# Voicecard-SMR-v04.net
KiCad netlist of a schematic drawn in EAGLE
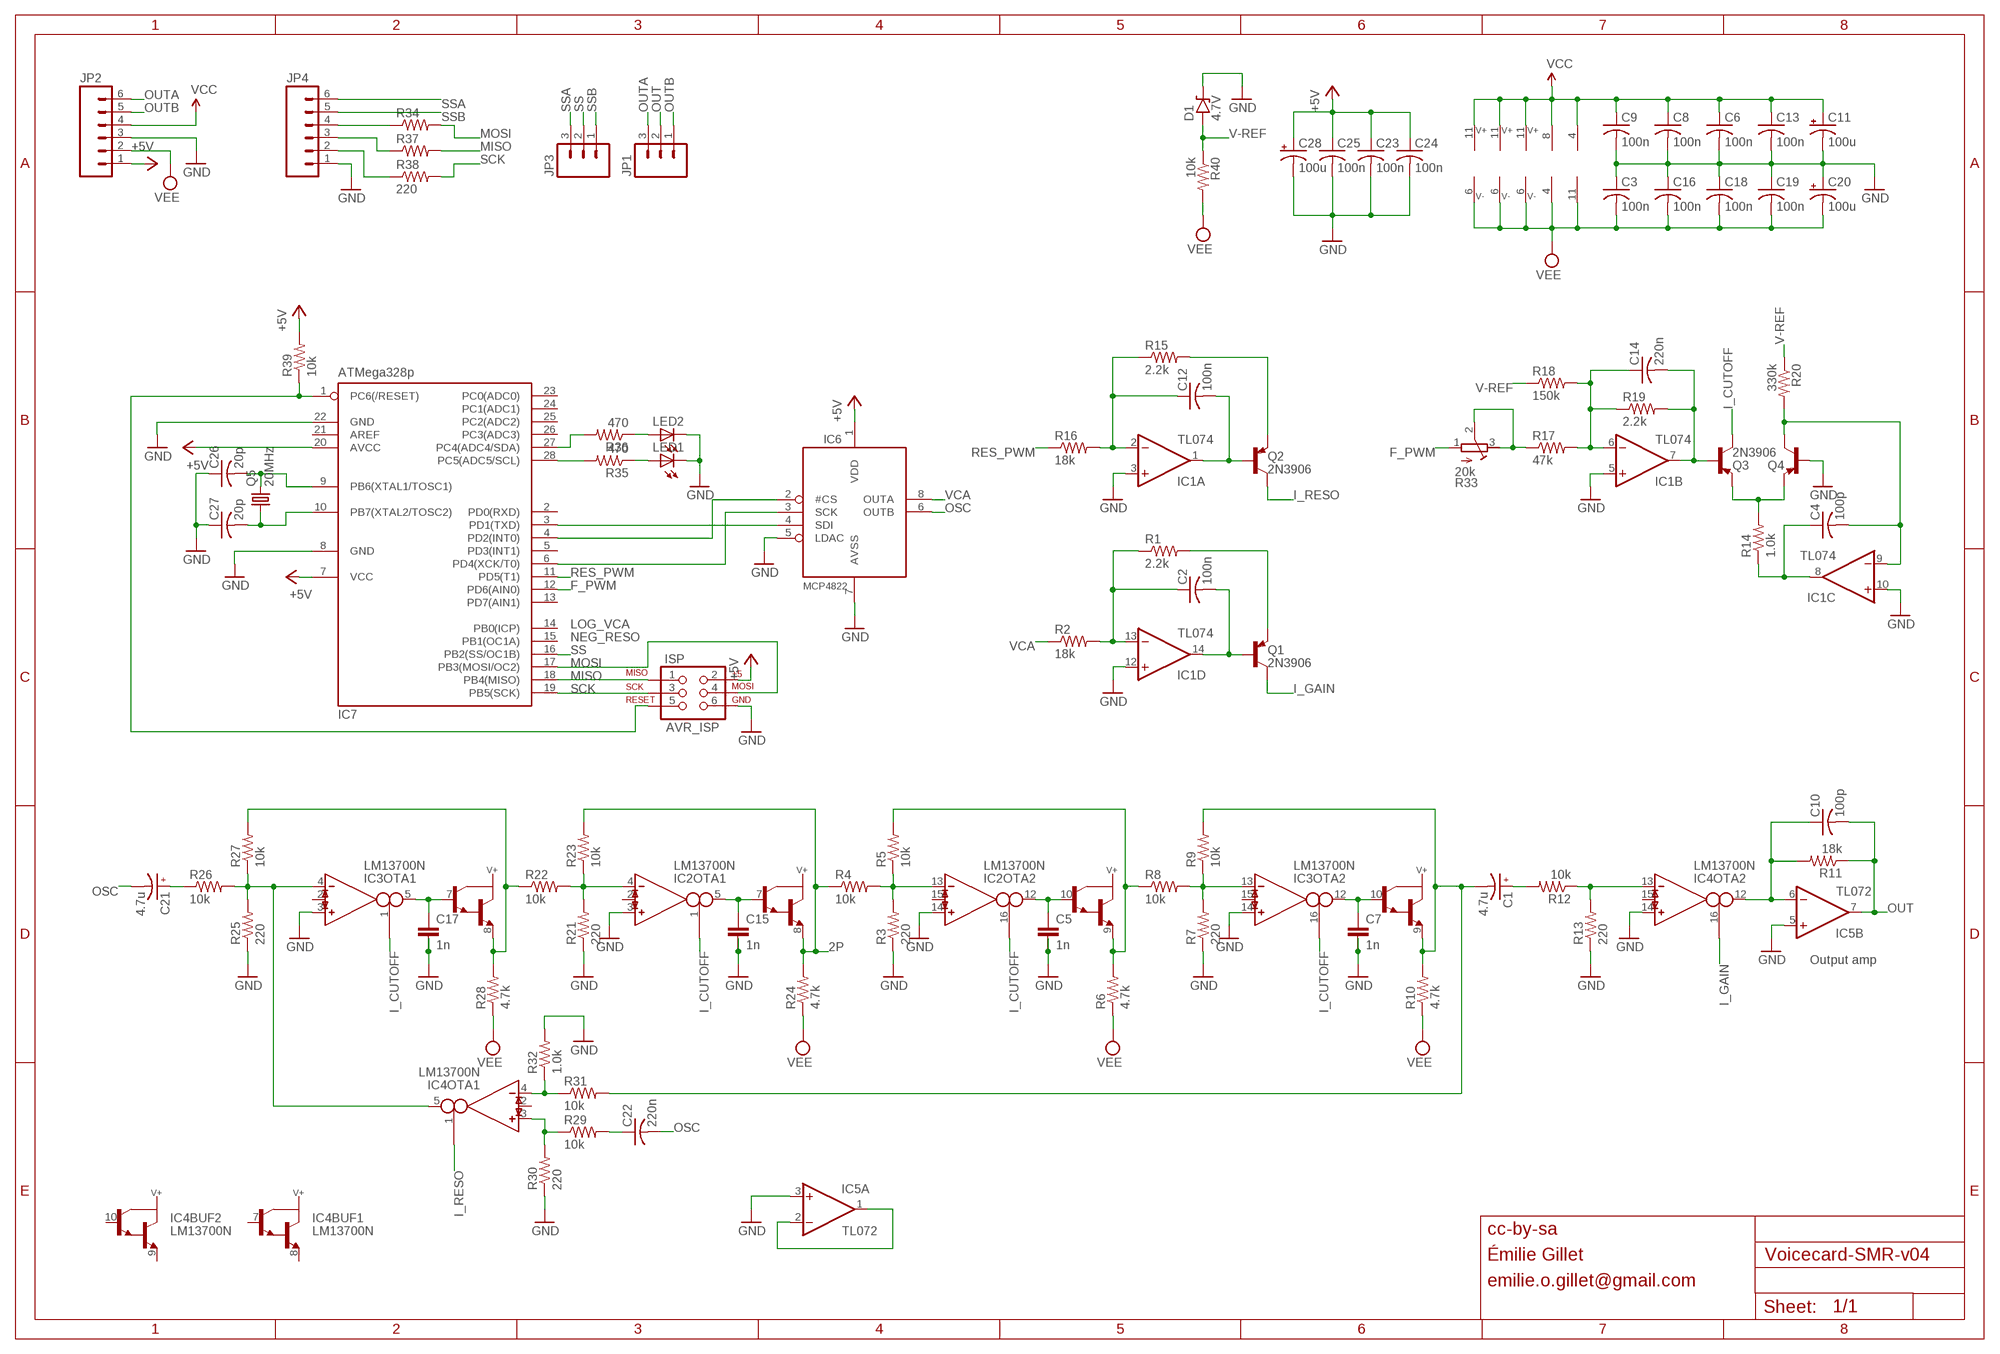
[diagram p0: schematic, sheet 1]

(export (version "E")
  (design (tool "Eeschema 10.0.6"))
  (components
    (comp (ref "C1")
      (value "4.7u")
      (footprint "eagle-import:E11-6.3")
      (libsource (lib "eagle-import") (part "CPOL-USE11-6.3"))
    )
    (comp (ref "C2")
      (value "100n")
      (footprint "eagle-import:C025-025X050")
      (libsource (lib "eagle-import") (part "C-US025-025X050"))
    )
    (comp (ref "C3")
      (value "100n")
      (footprint "eagle-import:C025-025X050")
      (libsource (lib "eagle-import") (part "C-US025-025X050"))
    )
    (comp (ref "C4")
      (value "100p")
      (footprint "eagle-import:C025-025X050")
      (libsource (lib "eagle-import") (part "C-US025-025X050"))
    )
    (comp (ref "C5")
      (value "1n")
      (footprint "eagle-import:C2.5_5-2")
      (libsource (lib "eagle-import") (part "C-2.5-5/2"))
    )
    (comp (ref "C6")
      (value "100n")
      (footprint "eagle-import:C025-025X050")
      (libsource (lib "eagle-import") (part "C-US025-025X050"))
    )
    (comp (ref "C7")
      (value "1n")
      (footprint "eagle-import:C2.5_5-2")
      (libsource (lib "eagle-import") (part "C-2.5-5/2"))
    )
    (comp (ref "C8")
      (value "100n")
      (footprint "eagle-import:C025-025X050")
      (libsource (lib "eagle-import") (part "C-US025-025X050"))
    )
    (comp (ref "C9")
      (value "100n")
      (footprint "eagle-import:C025-025X050")
      (libsource (lib "eagle-import") (part "C-US025-025X050"))
    )
    (comp (ref "C10")
      (value "100p")
      (footprint "eagle-import:C025-025X050")
      (libsource (lib "eagle-import") (part "C-US025-025X050"))
    )
    (comp (ref "C11")
      (value "100u")
      (footprint "eagle-import:E2,5-6")
      (libsource (lib "eagle-import") (part "CPOL-USE2.5-6"))
    )
    (comp (ref "C12")
      (value "100n")
      (footprint "eagle-import:C025-025X050")
      (libsource (lib "eagle-import") (part "C-US025-025X050"))
    )
    (comp (ref "C13")
      (value "100n")
      (footprint "eagle-import:C025-025X050")
      (libsource (lib "eagle-import") (part "C-US025-025X050"))
    )
    (comp (ref "C14")
      (value "220n")
      (footprint "eagle-import:C025-025X050")
      (libsource (lib "eagle-import") (part "C-US025-025X050"))
    )
    (comp (ref "C15")
      (value "1n")
      (footprint "eagle-import:C2.5_5-2")
      (libsource (lib "eagle-import") (part "C-2.5-5/2"))
    )
    (comp (ref "C16")
      (value "100n")
      (footprint "eagle-import:C025-025X050")
      (libsource (lib "eagle-import") (part "C-US025-025X050"))
    )
    (comp (ref "C17")
      (value "1n")
      (footprint "eagle-import:C2.5_5-2")
      (libsource (lib "eagle-import") (part "C-2.5-5/2"))
    )
    (comp (ref "C18")
      (value "100n")
      (footprint "eagle-import:C025-025X050")
      (libsource (lib "eagle-import") (part "C-US025-025X050"))
    )
    (comp (ref "C19")
      (value "100n")
      (footprint "eagle-import:C025-025X050")
      (libsource (lib "eagle-import") (part "C-US025-025X050"))
    )
    (comp (ref "C20")
      (value "100u")
      (footprint "eagle-import:E2,5-6")
      (libsource (lib "eagle-import") (part "CPOL-USE2.5-6"))
    )
    (comp (ref "C21")
      (value "4.7u")
      (footprint "eagle-import:E11-6.3")
      (libsource (lib "eagle-import") (part "CPOL-USE11-6.3"))
    )
    (comp (ref "C22")
      (value "220n")
      (footprint "eagle-import:C025-025X050")
      (libsource (lib "eagle-import") (part "C-US025-025X050"))
    )
    (comp (ref "C23")
      (value "100n")
      (footprint "eagle-import:C025-025X050")
      (libsource (lib "eagle-import") (part "C-US025-025X050"))
    )
    (comp (ref "C24")
      (value "100n")
      (footprint "eagle-import:C025-025X050")
      (libsource (lib "eagle-import") (part "C-US025-025X050"))
    )
    (comp (ref "C25")
      (value "100n")
      (footprint "eagle-import:C025-024X044")
      (libsource (lib "eagle-import") (part "C-US025-024X044"))
    )
    (comp (ref "C26")
      (value "20p")
      (footprint "eagle-import:C025-024X044")
      (libsource (lib "eagle-import") (part "C-US025-024X044"))
    )
    (comp (ref "C27")
      (value "20p")
      (footprint "eagle-import:C025-024X044")
      (libsource (lib "eagle-import") (part "C-US025-024X044"))
    )
    (comp (ref "C28")
      (value "100u")
      (footprint "eagle-import:E2,5-6")
      (libsource (lib "eagle-import") (part "CPOL-USE2.5-6"))
    )
    (comp (ref "D1")
      (value "4.7V")
      (footprint "eagle-import:D-5")
      (libsource (lib "eagle-import") (part "1N47XXDO35"))
    )
    (comp (ref "IC1")
      (value "TL074")
      (footprint "eagle-import:DIL14")
      (libsource (lib "eagle-import") (part "TL084P"))
    )
    (comp (ref "IC2")
      (value "LM13700N")
      (footprint "eagle-import:DIL16")
      (libsource (lib "eagle-import") (part "LM13700N"))
    )
    (comp (ref "IC3")
      (value "LM13700N")
      (footprint "eagle-import:DIL16")
      (libsource (lib "eagle-import") (part "LM13700N"))
    )
    (comp (ref "IC4")
      (value "LM13700N")
      (footprint "eagle-import:DIL16")
      (libsource (lib "eagle-import") (part "LM13700N"))
    )
    (comp (ref "IC5")
      (value "TL072")
      (footprint "eagle-import:DIL08")
      (libsource (lib "eagle-import") (part "TL072P"))
    )
    (comp (ref "IC6")
      (value "MCP4822")
      (footprint "eagle-import:DIL08")
      (libsource (lib "eagle-import") (part "MCP4822"))
    )
    (comp (ref "IC7")
      (value "ATMega328p")
      (footprint "eagle-import:DIL28-3")
      (libsource (lib "eagle-import") (part "MEGA8-P"))
    )
    (comp (ref "ISP")
      (value "AVR_ISP")
      (footprint "eagle-import:2X3")
      (libsource (lib "eagle-import") (part "AVR_SPI_PRG_6PTH"))
    )
    (comp (ref "JP1")
      (value "M03PTH")
      (footprint "eagle-import:1X03")
      (libsource (lib "eagle-import") (part "M03PTH"))
    )
    (comp (ref "JP2")
      (value "M06SIP")
      (footprint "eagle-import:1X06")
      (libsource (lib "eagle-import") (part "M06SIP"))
    )
    (comp (ref "JP3")
      (value "M03PTH")
      (footprint "eagle-import:1X03")
      (libsource (lib "eagle-import") (part "M03PTH"))
    )
    (comp (ref "JP4")
      (value "M06SIP")
      (footprint "eagle-import:1X06")
      (libsource (lib "eagle-import") (part "M06SIP"))
    )
    (comp (ref "LED1")
      (value "LED3MM")
      (footprint "eagle-import:LED3MM")
      (libsource (lib "eagle-import") (part "LED3MM"))
    )
    (comp (ref "LED2")
      (value "LED3MM")
      (footprint "eagle-import:LED3MM")
      (libsource (lib "eagle-import") (part "LED3MM"))
    )
    (comp (ref "Q1")
      (value "2N3906")
      (footprint "eagle-import:TO92-")
      (libsource (lib "eagle-import") (part "2N3906-"))
    )
    (comp (ref "Q2")
      (value "2N3906")
      (footprint "eagle-import:TO92-")
      (libsource (lib "eagle-import") (part "2N3906-"))
    )
    (comp (ref "Q3")
      (value "2N3906")
      (footprint "eagle-import:TO92-")
      (libsource (lib "eagle-import") (part "2N3906-"))
    )
    (comp (ref "Q4")
      (value "2N3906")
      (footprint "eagle-import:TO92-")
      (libsource (lib "eagle-import") (part "2N3906-"))
    )
    (comp (ref "Q5")
      (value "20MHz")
      (footprint "eagle-import:HC49U-V")
      (libsource (lib "eagle-import") (part "CRYSTALHC49U-V"))
    )
    (comp (ref "R1")
      (value "2.2k")
      (footprint "eagle-import:0204_7")
      (libsource (lib "eagle-import") (part "R-US_0204/7"))
    )
    (comp (ref "R2")
      (value "18k")
      (footprint "eagle-import:0204_7")
      (libsource (lib "eagle-import") (part "R-US_0204/7"))
    )
    (comp (ref "R3")
      (value "220")
      (footprint "eagle-import:0204_7")
      (libsource (lib "eagle-import") (part "R-US_0204/7"))
    )
    (comp (ref "R4")
      (value "10k")
      (footprint "eagle-import:0204_7")
      (libsource (lib "eagle-import") (part "R-US_0204/7"))
    )
    (comp (ref "R5")
      (value "10k")
      (footprint "eagle-import:0204_7")
      (libsource (lib "eagle-import") (part "R-US_0204/7"))
    )
    (comp (ref "R6")
      (value "4.7k")
      (footprint "eagle-import:0204_7")
      (libsource (lib "eagle-import") (part "R-US_0204/7"))
    )
    (comp (ref "R7")
      (value "220")
      (footprint "eagle-import:0204_7")
      (libsource (lib "eagle-import") (part "R-US_0204/7"))
    )
    (comp (ref "R8")
      (value "10k")
      (footprint "eagle-import:0204_7")
      (libsource (lib "eagle-import") (part "R-US_0204/7"))
    )
    (comp (ref "R9")
      (value "10k")
      (footprint "eagle-import:0204_7")
      (libsource (lib "eagle-import") (part "R-US_0204/7"))
    )
    (comp (ref "R10")
      (value "4.7k")
      (footprint "eagle-import:0204_7")
      (libsource (lib "eagle-import") (part "R-US_0204/7"))
    )
    (comp (ref "R11")
      (value "18k")
      (footprint "eagle-import:0204_7")
      (libsource (lib "eagle-import") (part "R-US_0204/7"))
    )
    (comp (ref "R12")
      (value "10k")
      (footprint "eagle-import:0204_7")
      (libsource (lib "eagle-import") (part "R-US_0204/7"))
    )
    (comp (ref "R13")
      (value "220")
      (footprint "eagle-import:0204_7")
      (libsource (lib "eagle-import") (part "R-US_0204/7"))
    )
    (comp (ref "R14")
      (value "1.0k")
      (footprint "eagle-import:0204_7")
      (libsource (lib "eagle-import") (part "R-US_0204/7"))
    )
    (comp (ref "R15")
      (value "2.2k")
      (footprint "eagle-import:0204_7")
      (libsource (lib "eagle-import") (part "R-US_0204/7"))
    )
    (comp (ref "R16")
      (value "18k")
      (footprint "eagle-import:0204_7")
      (libsource (lib "eagle-import") (part "R-US_0204/7"))
    )
    (comp (ref "R17")
      (value "47k")
      (footprint "eagle-import:0204_7")
      (libsource (lib "eagle-import") (part "R-US_0204/7"))
    )
    (comp (ref "R18")
      (value "150k")
      (footprint "eagle-import:0204_7")
      (libsource (lib "eagle-import") (part "R-US_0204/7"))
    )
    (comp (ref "R19")
      (value "2.2k")
      (footprint "eagle-import:0204_7")
      (libsource (lib "eagle-import") (part "R-US_0204/7"))
    )
    (comp (ref "R20")
      (value "330k")
      (footprint "eagle-import:0204_7")
      (libsource (lib "eagle-import") (part "R-US_0204/7"))
    )
    (comp (ref "R21")
      (value "220")
      (footprint "eagle-import:0204_7")
      (libsource (lib "eagle-import") (part "R-US_0204/7"))
    )
    (comp (ref "R22")
      (value "10k")
      (footprint "eagle-import:0204_7")
      (libsource (lib "eagle-import") (part "R-US_0204/7"))
    )
    (comp (ref "R23")
      (value "10k")
      (footprint "eagle-import:0204_7")
      (libsource (lib "eagle-import") (part "R-US_0204/7"))
    )
    (comp (ref "R24")
      (value "4.7k")
      (footprint "eagle-import:0204_7")
      (libsource (lib "eagle-import") (part "R-US_0204/7"))
    )
    (comp (ref "R25")
      (value "220")
      (footprint "eagle-import:0204_7")
      (libsource (lib "eagle-import") (part "R-US_0204/7"))
    )
    (comp (ref "R26")
      (value "10k")
      (footprint "eagle-import:0204_7")
      (libsource (lib "eagle-import") (part "R-US_0204/7"))
    )
    (comp (ref "R27")
      (value "10k")
      (footprint "eagle-import:0204_7")
      (libsource (lib "eagle-import") (part "R-US_0204/7"))
    )
    (comp (ref "R28")
      (value "4.7k")
      (footprint "eagle-import:0204_7")
      (libsource (lib "eagle-import") (part "R-US_0204/7"))
    )
    (comp (ref "R29")
      (value "10k")
      (footprint "eagle-import:0204_7")
      (libsource (lib "eagle-import") (part "R-US_0204/7"))
    )
    (comp (ref "R30")
      (value "220")
      (footprint "eagle-import:0204_7")
      (libsource (lib "eagle-import") (part "R-US_0204/7"))
    )
    (comp (ref "R31")
      (value "10k")
      (footprint "eagle-import:0204_7")
      (libsource (lib "eagle-import") (part "R-US_0204/7"))
    )
    (comp (ref "R32")
      (value "1.0k")
      (footprint "eagle-import:0204_7")
      (libsource (lib "eagle-import") (part "R-US_0204/7"))
    )
    (comp (ref "R33")
      (value "20k")
      (footprint "eagle-import:RTRIM3296P")
      (libsource (lib "eagle-import") (part "R-TRIMM3296P"))
    )
    (comp (ref "R34")
      (value "220")
      (footprint "eagle-import:0204_7")
      (libsource (lib "eagle-import") (part "R-US_0204/7"))
    )
    (comp (ref "R35")
      (value "470")
      (footprint "eagle-import:0204_7")
      (libsource (lib "eagle-import") (part "R-US_0204/7"))
    )
    (comp (ref "R36")
      (value "470")
      (footprint "eagle-import:0204_7")
      (libsource (lib "eagle-import") (part "R-US_0204/7"))
    )
    (comp (ref "R37")
      (value "220")
      (footprint "eagle-import:0204_7")
      (libsource (lib "eagle-import") (part "R-US_0204/7"))
    )
    (comp (ref "R38")
      (value "220")
      (footprint "eagle-import:0204_7")
      (libsource (lib "eagle-import") (part "R-US_0204/7"))
    )
    (comp (ref "R39")
      (value "10k")
      (footprint "eagle-import:0204_7")
      (libsource (lib "eagle-import") (part "R-US_0204/7"))
    )
    (comp (ref "R40")
      (value "10k")
      (footprint "eagle-import:0204_7")
      (libsource (lib "eagle-import") (part "R-US_0204/7"))
    )
  )
  (nets
    (net (code "1") (name "+5V") (class "Default")
      (node (ref "C23") (pin "1") (pinfunction "1_1") (pintype "passive"))
      (node (ref "C24") (pin "1") (pinfunction "1_1") (pintype "passive"))
      (node (ref "C25") (pin "1") (pinfunction "1_1") (pintype "passive"))
      (node (ref "C28") (pin "+") (pinfunction "+_+") (pintype "passive"))
      (node (ref "IC6") (pin "1") (pinfunction "VDD_1") (pintype "power_in"))
      (node (ref "IC7") (pin "20") (pinfunction "AVCC_20") (pintype "power_in"))
      (node (ref "IC7") (pin "7") (pinfunction "VCC_7") (pintype "power_in"))
      (node (ref "ISP") (pin "2") (pinfunction "2_2") (pintype "passive"))
      (node (ref "JP2") (pin "1") (pinfunction "1_1") (pintype "passive"))
      (node (ref "R39") (pin "2") (pinfunction "2_2") (pintype "passive"))
    )
    (net (code "2") (name "/2P") (class "Default")
      (node (ref "IC2") (pin "8") (pinfunction "E_8") (pintype "passive"))
      (node (ref "R23") (pin "2") (pinfunction "2_2") (pintype "passive"))
      (node (ref "R24") (pin "2") (pinfunction "2_2") (pintype "passive"))
      (node (ref "R4") (pin "1") (pinfunction "1_1") (pintype "passive"))
    )
    (net (code "3") (name "/F_PWM") (class "Default")
      (node (ref "IC7") (pin "12") (pinfunction "PD6(AIN0)_12") (pintype "bidirectional"))
      (node (ref "R33") (pin "1") (pinfunction "E_1") (pintype "passive"))
    )
    (net (code "4") (name "/I_CUTOFF") (class "Default")
      (node (ref "IC2") (pin "1") (pinfunction "I_BIAS_1") (pintype "input"))
      (node (ref "IC2") (pin "16") (pinfunction "I_BIAS_16") (pintype "input"))
      (node (ref "IC3") (pin "1") (pinfunction "I_BIAS_1") (pintype "input"))
      (node (ref "IC3") (pin "16") (pinfunction "I_BIAS_16") (pintype "input"))
      (node (ref "Q3") (pin "1") (pinfunction "C_1") (pintype "passive"))
    )
    (net (code "5") (name "/I_GAIN") (class "Default")
      (node (ref "IC4") (pin "16") (pinfunction "I_BIAS_16") (pintype "input"))
      (node (ref "Q1") (pin "1") (pinfunction "C_1") (pintype "passive"))
    )
    (net (code "6") (name "/I_RESO") (class "Default")
      (node (ref "IC4") (pin "1") (pinfunction "I_BIAS_1") (pintype "input"))
      (node (ref "Q2") (pin "1") (pinfunction "C_1") (pintype "passive"))
    )
    (net (code "7") (name "/MISO") (class "Default")
      (node (ref "IC7") (pin "18") (pinfunction "PB4(MISO)_18") (pintype "bidirectional"))
      (node (ref "ISP") (pin "1") (pinfunction "1_1") (pintype "passive"))
      (node (ref "R37") (pin "2") (pinfunction "2_2") (pintype "passive"))
    )
    (net (code "8") (name "/MOSI") (class "Default")
      (node (ref "IC7") (pin "17") (pinfunction "PB3(MOSI/OC2)_17") (pintype "bidirectional"))
      (node (ref "ISP") (pin "4") (pinfunction "4_4") (pintype "passive"))
      (node (ref "R34") (pin "2") (pinfunction "2_2") (pintype "passive"))
    )
    (net (code "9") (name "/OSC") (class "Default")
      (node (ref "C21") (pin "-") (pinfunction "2_-") (pintype "passive"))
      (node (ref "C22") (pin "2") (pinfunction "2_2") (pintype "passive"))
      (node (ref "IC6") (pin "6") (pinfunction "OUTB_6") (pintype "output"))
    )
    (net (code "10") (name "/OUT") (class "Default")
      (node (ref "C10") (pin "2") (pinfunction "2_2") (pintype "passive"))
      (node (ref "IC5") (pin "7") (pinfunction "OUT_7") (pintype "output"))
      (node (ref "JP1") (pin "2") (pinfunction "2_2") (pintype "passive"))
      (node (ref "R11") (pin "1") (pinfunction "1_1") (pintype "passive"))
    )
    (net (code "11") (name "/OUTA") (class "Default")
      (node (ref "JP1") (pin "3") (pinfunction "3_3") (pintype "passive"))
      (node (ref "JP2") (pin "6") (pinfunction "6_6") (pintype "passive"))
    )
    (net (code "12") (name "/OUTB") (class "Default")
      (node (ref "JP1") (pin "1") (pinfunction "1_1") (pintype "passive"))
      (node (ref "JP2") (pin "5") (pinfunction "5_5") (pintype "passive"))
    )
    (net (code "13") (name "/RES_PWM") (class "Default")
      (node (ref "IC7") (pin "11") (pinfunction "PD5(T1)_11") (pintype "bidirectional"))
      (node (ref "R16") (pin "1") (pinfunction "1_1") (pintype "passive"))
    )
    (net (code "14") (name "/SCK") (class "Default")
      (node (ref "IC7") (pin "19") (pinfunction "PB5(SCK)_19") (pintype "bidirectional"))
      (node (ref "ISP") (pin "3") (pinfunction "3_3") (pintype "passive"))
      (node (ref "R38") (pin "2") (pinfunction "2_2") (pintype "passive"))
    )
    (net (code "15") (name "/SS") (class "Default")
      (node (ref "IC7") (pin "16") (pinfunction "PB2(SS/OC1B)_16") (pintype "bidirectional"))
      (node (ref "JP3") (pin "2") (pinfunction "2_2") (pintype "passive"))
    )
    (net (code "16") (name "/SSA") (class "Default")
      (node (ref "JP3") (pin "3") (pinfunction "3_3") (pintype "passive"))
      (node (ref "JP4") (pin "6") (pinfunction "6_6") (pintype "passive"))
    )
    (net (code "17") (name "/SSB") (class "Default")
      (node (ref "JP3") (pin "1") (pinfunction "1_1") (pintype "passive"))
      (node (ref "JP4") (pin "5") (pinfunction "5_5") (pintype "passive"))
    )
    (net (code "18") (name "/V-REF") (class "Default")
      (node (ref "D1") (pin "A") (pinfunction "A_A") (pintype "passive"))
      (node (ref "R18") (pin "1") (pinfunction "1_1") (pintype "passive"))
      (node (ref "R20") (pin "1") (pinfunction "1_1") (pintype "passive"))
      (node (ref "R40") (pin "1") (pinfunction "1_1") (pintype "passive"))
    )
    (net (code "19") (name "/VCA") (class "Default")
      (node (ref "IC6") (pin "8") (pinfunction "OUTA_8") (pintype "output"))
      (node (ref "R2") (pin "1") (pinfunction "1_1") (pintype "passive"))
    )
    (net (code "20") (name "GND") (class "Default")
      (node (ref "C11") (pin "-") (pinfunction "-_-") (pintype "passive"))
      (node (ref "C13") (pin "2") (pinfunction "2_2") (pintype "passive"))
      (node (ref "C15") (pin "2") (pinfunction "2_2") (pintype "passive"))
      (node (ref "C15") (pin "3") (pinfunction "3_3") (pintype "passive"))
      (node (ref "C16") (pin "1") (pinfunction "1_1") (pintype "passive"))
      (node (ref "C17") (pin "2") (pinfunction "2_2") (pintype "passive"))
      (node (ref "C17") (pin "3") (pinfunction "3_3") (pintype "passive"))
      (node (ref "C18") (pin "1") (pinfunction "1_1") (pintype "passive"))
      (node (ref "C19") (pin "1") (pinfunction "1_1") (pintype "passive"))
      (node (ref "C20") (pin "+") (pinfunction "+_+") (pintype "passive"))
      (node (ref "C23") (pin "2") (pinfunction "2_2") (pintype "passive"))
      (node (ref "C24") (pin "2") (pinfunction "2_2") (pintype "passive"))
      (node (ref "C25") (pin "2") (pinfunction "2_2") (pintype "passive"))
      (node (ref "C26") (pin "1") (pinfunction "1_1") (pintype "passive"))
      (node (ref "C27") (pin "1") (pinfunction "1_1") (pintype "passive"))
      (node (ref "C28") (pin "-") (pinfunction "-_-") (pintype "passive"))
      (node (ref "C3") (pin "1") (pinfunction "1_1") (pintype "passive"))
      (node (ref "C5") (pin "2") (pinfunction "2_2") (pintype "passive"))
      (node (ref "C5") (pin "3") (pinfunction "3_3") (pintype "passive"))
      (node (ref "C6") (pin "2") (pinfunction "2_2") (pintype "passive"))
      (node (ref "C7") (pin "2") (pinfunction "2_2") (pintype "passive"))
      (node (ref "C7") (pin "3") (pinfunction "3_3") (pintype "passive"))
      (node (ref "C8") (pin "2") (pinfunction "2_2") (pintype "passive"))
      (node (ref "C9") (pin "2") (pinfunction "2_2") (pintype "passive"))
      (node (ref "D1") (pin "C") (pinfunction "C_C") (pintype "passive"))
      (node (ref "IC1") (pin "10") (pinfunction "+IN_10") (pintype "input"))
      (node (ref "IC1") (pin "12") (pinfunction "+IN_12") (pintype "input"))
      (node (ref "IC1") (pin "3") (pinfunction "+IN_3") (pintype "input"))
      (node (ref "IC1") (pin "5") (pinfunction "+IN_5") (pintype "input"))
      (node (ref "IC2") (pin "14") (pinfunction "IN_P_14") (pintype "input"))
      (node (ref "IC2") (pin "3") (pinfunction "IN_P_3") (pintype "input"))
      (node (ref "IC3") (pin "14") (pinfunction "IN_P_14") (pintype "input"))
      (node (ref "IC3") (pin "3") (pinfunction "IN_P_3") (pintype "input"))
      (node (ref "IC4") (pin "14") (pinfunction "IN_P_14") (pintype "input"))
      (node (ref "IC5") (pin "3") (pinfunction "+IN_3") (pintype "input"))
      (node (ref "IC5") (pin "5") (pinfunction "+IN_5") (pintype "input"))
      (node (ref "IC6") (pin "5") (pinfunction "LDAC_5") (pintype "input"))
      (node (ref "IC6") (pin "7") (pinfunction "AVSS_7") (pintype "power_in"))
      (node (ref "IC7") (pin "22") (pinfunction "GND_22") (pintype "power_in"))
      (node (ref "IC7") (pin "8") (pinfunction "GND_8") (pintype "power_in"))
      (node (ref "ISP") (pin "6") (pinfunction "6_6") (pintype "passive"))
      (node (ref "JP2") (pin "3") (pinfunction "3_3") (pintype "passive"))
      (node (ref "JP4") (pin "1") (pinfunction "1_1") (pintype "passive"))
      (node (ref "LED1") (pin "K") (pinfunction "C_K") (pintype "passive"))
      (node (ref "LED2") (pin "K") (pinfunction "C_K") (pintype "passive"))
      (node (ref "Q4") (pin "2") (pinfunction "B_2") (pintype "passive"))
      (node (ref "R13") (pin "1") (pinfunction "1_1") (pintype "passive"))
      (node (ref "R21") (pin "1") (pinfunction "1_1") (pintype "passive"))
      (node (ref "R25") (pin "1") (pinfunction "1_1") (pintype "passive"))
      (node (ref "R3") (pin "1") (pinfunction "1_1") (pintype "passive"))
      (node (ref "R30") (pin "1") (pinfunction "1_1") (pintype "passive"))
      (node (ref "R32") (pin "2") (pinfunction "2_2") (pintype "passive"))
      (node (ref "R7") (pin "1") (pinfunction "1_1") (pintype "passive"))
    )
    (net (code "21") (name "Net-(C1-1)") (class "Default")
      (node (ref "C1") (pin "+") (pinfunction "1_+") (pintype "passive"))
      (node (ref "R12") (pin "2") (pinfunction "2_2") (pintype "passive"))
    )
    (net (code "22") (name "Net-(C1-2)") (class "Default")
      (node (ref "C1") (pin "-") (pinfunction "2_-") (pintype "passive"))
      (node (ref "IC3") (pin "9") (pinfunction "E_9") (pintype "passive"))
      (node (ref "R10") (pin "2") (pinfunction "2_2") (pintype "passive"))
      (node (ref "R31") (pin "2") (pinfunction "2_2") (pintype "passive"))
      (node (ref "R9") (pin "2") (pinfunction "2_2") (pintype "passive"))
    )
    (net (code "23") (name "Net-(C21-1)") (class "Default")
      (node (ref "C21") (pin "+") (pinfunction "1_+") (pintype "passive"))
      (node (ref "R26") (pin "1") (pinfunction "1_1") (pintype "passive"))
    )
    (net (code "24") (name "Net-(C22-Pad1)") (class "Default")
      (node (ref "C22") (pin "1") (pinfunction "1_1") (pintype "passive"))
      (node (ref "R29") (pin "2") (pinfunction "2_2") (pintype "passive"))
    )
    (net (code "25") (name "Net-(IC1A--IN)") (class "Default")
      (node (ref "C12") (pin "1") (pinfunction "1_1") (pintype "passive"))
      (node (ref "IC1") (pin "2") (pinfunction "-IN_2") (pintype "input"))
      (node (ref "R15") (pin "1") (pinfunction "1_1") (pintype "passive"))
      (node (ref "R16") (pin "2") (pinfunction "2_2") (pintype "passive"))
    )
    (net (code "26") (name "Net-(IC1A-OUT)") (class "Default")
      (node (ref "C12") (pin "2") (pinfunction "2_2") (pintype "passive"))
      (node (ref "IC1") (pin "1") (pinfunction "OUT_1") (pintype "output"))
      (node (ref "Q2") (pin "2") (pinfunction "B_2") (pintype "passive"))
    )
    (net (code "27") (name "Net-(IC1B--IN)") (class "Default")
      (node (ref "C14") (pin "1") (pinfunction "1_1") (pintype "passive"))
      (node (ref "IC1") (pin "6") (pinfunction "-IN_6") (pintype "input"))
      (node (ref "R17") (pin "2") (pinfunction "2_2") (pintype "passive"))
      (node (ref "R18") (pin "2") (pinfunction "2_2") (pintype "passive"))
      (node (ref "R19") (pin "1") (pinfunction "1_1") (pintype "passive"))
    )
    (net (code "28") (name "Net-(IC1B-OUT)") (class "Default")
      (node (ref "C14") (pin "2") (pinfunction "2_2") (pintype "passive"))
      (node (ref "IC1") (pin "7") (pinfunction "OUT_7") (pintype "output"))
      (node (ref "Q3") (pin "2") (pinfunction "B_2") (pintype "passive"))
      (node (ref "R19") (pin "2") (pinfunction "2_2") (pintype "passive"))
    )
    (net (code "29") (name "Net-(IC1C--IN)") (class "Default")
      (node (ref "C4") (pin "2") (pinfunction "2_2") (pintype "passive"))
      (node (ref "IC1") (pin "9") (pinfunction "-IN_9") (pintype "input"))
      (node (ref "Q4") (pin "1") (pinfunction "C_1") (pintype "passive"))
      (node (ref "R20") (pin "2") (pinfunction "2_2") (pintype "passive"))
    )
    (net (code "30") (name "Net-(IC1C-OUT)") (class "Default")
      (node (ref "C4") (pin "1") (pinfunction "1_1") (pintype "passive"))
      (node (ref "IC1") (pin "8") (pinfunction "OUT_8") (pintype "output"))
      (node (ref "R14") (pin "1") (pinfunction "1_1") (pintype "passive"))
    )
    (net (code "31") (name "Net-(IC1D--IN)") (class "Default")
      (node (ref "C2") (pin "1") (pinfunction "1_1") (pintype "passive"))
      (node (ref "IC1") (pin "13") (pinfunction "-IN_13") (pintype "input"))
      (node (ref "R1") (pin "1") (pinfunction "1_1") (pintype "passive"))
      (node (ref "R2") (pin "2") (pinfunction "2_2") (pintype "passive"))
    )
    (net (code "32") (name "Net-(IC1D-OUT)") (class "Default")
      (node (ref "C2") (pin "2") (pinfunction "2_2") (pintype "passive"))
      (node (ref "IC1") (pin "14") (pinfunction "OUT_14") (pintype "output"))
      (node (ref "Q1") (pin "2") (pinfunction "B_2") (pintype "passive"))
    )
    (net (code "33") (name "Net-(IC2A-B)") (class "Default")
      (node (ref "C15") (pin "1") (pinfunction "1_1") (pintype "passive"))
      (node (ref "IC2") (pin "5") (pinfunction "OUT_5") (pintype "output"))
      (node (ref "IC2") (pin "7") (pinfunction "B_7") (pintype "passive"))
    )
    (net (code "34") (name "Net-(IC2B-B)") (class "Default")
      (node (ref "C5") (pin "1") (pinfunction "1_1") (pintype "passive"))
      (node (ref "IC2") (pin "10") (pinfunction "B_10") (pintype "passive"))
      (node (ref "IC2") (pin "12") (pinfunction "OUT_12") (pintype "output"))
    )
    (net (code "35") (name "Net-(IC2B-E)") (class "Default")
      (node (ref "IC2") (pin "9") (pinfunction "E_9") (pintype "passive"))
      (node (ref "R5") (pin "2") (pinfunction "2_2") (pintype "passive"))
      (node (ref "R6") (pin "2") (pinfunction "2_2") (pintype "passive"))
      (node (ref "R8") (pin "1") (pinfunction "1_1") (pintype "passive"))
    )
    (net (code "36") (name "Net-(IC2C-IN_N)") (class "Default")
      (node (ref "IC2") (pin "4") (pinfunction "IN_N_4") (pintype "input"))
      (node (ref "R21") (pin "2") (pinfunction "2_2") (pintype "passive"))
      (node (ref "R22") (pin "2") (pinfunction "2_2") (pintype "passive"))
      (node (ref "R23") (pin "1") (pinfunction "1_1") (pintype "passive"))
    )
    (net (code "37") (name "Net-(IC2D-IN_N)") (class "Default")
      (node (ref "IC2") (pin "13") (pinfunction "IN_N_13") (pintype "input"))
      (node (ref "R3") (pin "2") (pinfunction "2_2") (pintype "passive"))
      (node (ref "R4") (pin "2") (pinfunction "2_2") (pintype "passive"))
      (node (ref "R5") (pin "1") (pinfunction "1_1") (pintype "passive"))
    )
    (net (code "38") (name "Net-(IC3A-B)") (class "Default")
      (node (ref "C17") (pin "1") (pinfunction "1_1") (pintype "passive"))
      (node (ref "IC3") (pin "5") (pinfunction "OUT_5") (pintype "output"))
      (node (ref "IC3") (pin "7") (pinfunction "B_7") (pintype "passive"))
    )
    (net (code "39") (name "Net-(IC3A-E)") (class "Default")
      (node (ref "IC3") (pin "8") (pinfunction "E_8") (pintype "passive"))
      (node (ref "R22") (pin "1") (pinfunction "1_1") (pintype "passive"))
      (node (ref "R27") (pin "2") (pinfunction "2_2") (pintype "passive"))
      (node (ref "R28") (pin "2") (pinfunction "2_2") (pintype "passive"))
    )
    (net (code "40") (name "Net-(IC3B-B)") (class "Default")
      (node (ref "C7") (pin "1") (pinfunction "1_1") (pintype "passive"))
      (node (ref "IC3") (pin "10") (pinfunction "B_10") (pintype "passive"))
      (node (ref "IC3") (pin "12") (pinfunction "OUT_12") (pintype "output"))
    )
    (net (code "41") (name "Net-(IC3C-IN_N)") (class "Default")
      (node (ref "IC3") (pin "4") (pinfunction "IN_N_4") (pintype "input"))
      (node (ref "IC4") (pin "5") (pinfunction "OUT_5") (pintype "output"))
      (node (ref "R25") (pin "2") (pinfunction "2_2") (pintype "passive"))
      (node (ref "R26") (pin "2") (pinfunction "2_2") (pintype "passive"))
      (node (ref "R27") (pin "1") (pinfunction "1_1") (pintype "passive"))
    )
    (net (code "42") (name "Net-(IC3D-IN_N)") (class "Default")
      (node (ref "IC3") (pin "13") (pinfunction "IN_N_13") (pintype "input"))
      (node (ref "R7") (pin "2") (pinfunction "2_2") (pintype "passive"))
      (node (ref "R8") (pin "2") (pinfunction "2_2") (pintype "passive"))
      (node (ref "R9") (pin "1") (pinfunction "1_1") (pintype "passive"))
    )
    (net (code "43") (name "Net-(IC4C-IN_N)") (class "Default")
      (node (ref "IC4") (pin "4") (pinfunction "IN_N_4") (pintype "input"))
      (node (ref "R31") (pin "1") (pinfunction "1_1") (pintype "passive"))
      (node (ref "R32") (pin "1") (pinfunction "1_1") (pintype "passive"))
    )
    (net (code "44") (name "Net-(IC4C-IN_P)") (class "Default")
      (node (ref "IC4") (pin "3") (pinfunction "IN_P_3") (pintype "input"))
      (node (ref "R29") (pin "1") (pinfunction "1_1") (pintype "passive"))
      (node (ref "R30") (pin "2") (pinfunction "2_2") (pintype "passive"))
    )
    (net (code "45") (name "Net-(IC4D-IN_N)") (class "Default")
      (node (ref "IC4") (pin "13") (pinfunction "IN_N_13") (pintype "input"))
      (node (ref "R12") (pin "1") (pinfunction "1_1") (pintype "passive"))
      (node (ref "R13") (pin "2") (pinfunction "2_2") (pintype "passive"))
    )
    (net (code "46") (name "Net-(IC4D-OUT)") (class "Default")
      (node (ref "C10") (pin "1") (pinfunction "1_1") (pintype "passive"))
      (node (ref "IC4") (pin "12") (pinfunction "OUT_12") (pintype "output"))
      (node (ref "IC5") (pin "6") (pinfunction "-IN_6") (pintype "input"))
      (node (ref "R11") (pin "2") (pinfunction "2_2") (pintype "passive"))
    )
    (net (code "47") (name "Net-(IC5A--IN)") (class "Default")
      (node (ref "IC5") (pin "1") (pinfunction "OUT_1") (pintype "output"))
      (node (ref "IC5") (pin "2") (pinfunction "-IN_2") (pintype "input"))
    )
    (net (code "48") (name "Net-(IC6-#CS)") (class "Default")
      (node (ref "IC6") (pin "2") (pinfunction "#CS_2") (pintype "input"))
      (node (ref "IC7") (pin "4") (pinfunction "PD2(INT0)_4") (pintype "bidirectional"))
    )
    (net (code "49") (name "Net-(IC6-SCK)") (class "Default")
      (node (ref "IC6") (pin "3") (pinfunction "SCK_3") (pintype "input"))
      (node (ref "IC7") (pin "6") (pinfunction "PD4(XCK/T0)_6") (pintype "bidirectional"))
    )
    (net (code "50") (name "Net-(IC6-SDI)") (class "Default")
      (node (ref "IC6") (pin "4") (pinfunction "SDI_4") (pintype "input"))
      (node (ref "IC7") (pin "3") (pinfunction "PD1(TXD)_3") (pintype "bidirectional"))
    )
    (net (code "51") (name "Net-(IC7-PB6(XTAL1{slash}TOSC1))") (class "Default")
      (node (ref "C26") (pin "2") (pinfunction "2_2") (pintype "passive"))
      (node (ref "IC7") (pin "9") (pinfunction "PB6(XTAL1/TOSC1)_9") (pintype "bidirectional"))
      (node (ref "Q5") (pin "2") (pinfunction "2_2") (pintype "passive"))
    )
    (net (code "52") (name "Net-(IC7-PB7(XTAL2{slash}TOSC2))") (class "Default")
      (node (ref "C27") (pin "2") (pinfunction "2_2") (pintype "passive"))
      (node (ref "IC7") (pin "10") (pinfunction "PB7(XTAL2/TOSC2)_10") (pintype "bidirectional"))
      (node (ref "Q5") (pin "1") (pinfunction "1_1") (pintype "passive"))
    )
    (net (code "53") (name "Net-(IC7-PC4(ADC4{slash}SDA))") (class "Default")
      (node (ref "IC7") (pin "27") (pinfunction "PC4(ADC4/SDA)_27") (pintype "bidirectional"))
      (node (ref "R36") (pin "2") (pinfunction "2_2") (pintype "passive"))
    )
    (net (code "54") (name "Net-(IC7-PC5(ADC5{slash}SCL))") (class "Default")
      (node (ref "IC7") (pin "28") (pinfunction "PC5(ADC5/SCL)_28") (pintype "bidirectional"))
      (node (ref "R35") (pin "2") (pinfunction "2_2") (pintype "passive"))
    )
    (net (code "55") (name "Net-(IC7-PC6({slash}RESET))") (class "Default")
      (node (ref "IC7") (pin "1") (pinfunction "PC6(/RESET)_1") (pintype "bidirectional"))
      (node (ref "ISP") (pin "5") (pinfunction "5_5") (pintype "passive"))
      (node (ref "R39") (pin "1") (pinfunction "1_1") (pintype "passive"))
    )
    (net (code "56") (name "Net-(JP4-Pad2)") (class "Default")
      (node (ref "JP4") (pin "2") (pinfunction "2_2") (pintype "passive"))
      (node (ref "R38") (pin "1") (pinfunction "1_1") (pintype "passive"))
    )
    (net (code "57") (name "Net-(JP4-Pad3)") (class "Default")
      (node (ref "JP4") (pin "3") (pinfunction "3_3") (pintype "passive"))
      (node (ref "R37") (pin "1") (pinfunction "1_1") (pintype "passive"))
    )
    (net (code "58") (name "Net-(JP4-Pad4)") (class "Default")
      (node (ref "JP4") (pin "4") (pinfunction "4_4") (pintype "passive"))
      (node (ref "R34") (pin "1") (pinfunction "1_1") (pintype "passive"))
    )
    (net (code "59") (name "Net-(LED1-PadA)") (class "Default")
      (node (ref "LED1") (pin "A") (pinfunction "A_A") (pintype "passive"))
      (node (ref "R35") (pin "1") (pinfunction "1_1") (pintype "passive"))
    )
    (net (code "60") (name "Net-(LED2-PadA)") (class "Default")
      (node (ref "LED2") (pin "A") (pinfunction "A_A") (pintype "passive"))
      (node (ref "R36") (pin "1") (pinfunction "1_1") (pintype "passive"))
    )
    (net (code "61") (name "Net-(Q1-E)") (class "Default")
      (node (ref "Q1") (pin "3") (pinfunction "E_3") (pintype "passive"))
      (node (ref "R1") (pin "2") (pinfunction "2_2") (pintype "passive"))
    )
    (net (code "62") (name "Net-(Q2-E)") (class "Default")
      (node (ref "Q2") (pin "3") (pinfunction "E_3") (pintype "passive"))
      (node (ref "R15") (pin "2") (pinfunction "2_2") (pintype "passive"))
    )
    (net (code "63") (name "Net-(Q3-E)") (class "Default")
      (node (ref "Q3") (pin "3") (pinfunction "E_3") (pintype "passive"))
      (node (ref "Q4") (pin "3") (pinfunction "E_3") (pintype "passive"))
      (node (ref "R14") (pin "2") (pinfunction "2_2") (pintype "passive"))
    )
    (net (code "64") (name "Net-(R33-A)") (class "Default")
      (node (ref "R17") (pin "1") (pinfunction "1_1") (pintype "passive"))
      (node (ref "R33") (pin "2") (pinfunction "S_2") (pintype "passive"))
      (node (ref "R33") (pin "3") (pinfunction "A_3") (pintype "passive"))
    )
    (net (code "65") (name "VCC") (class "Default")
      (node (ref "C11") (pin "+") (pinfunction "+_+") (pintype "passive"))
      (node (ref "C13") (pin "1") (pinfunction "1_1") (pintype "passive"))
      (node (ref "C6") (pin "1") (pinfunction "1_1") (pintype "passive"))
      (node (ref "C8") (pin "1") (pinfunction "1_1") (pintype "passive"))
      (node (ref "C9") (pin "1") (pinfunction "1_1") (pintype "passive"))
      (node (ref "IC1") (pin "4") (pinfunction "V+_4") (pintype "power_in"))
      (node (ref "IC2") (pin "11") (pinfunction "V+_11") (pintype "power_in"))
      (node (ref "IC3") (pin "11") (pinfunction "V+_11") (pintype "power_in"))
      (node (ref "IC4") (pin "11") (pinfunction "V+_11") (pintype "power_in"))
      (node (ref "IC5") (pin "8") (pinfunction "V+_8") (pintype "power_in"))
      (node (ref "JP2") (pin "4") (pinfunction "4_4") (pintype "passive"))
    )
    (net (code "66") (name "VEE") (class "Default")
      (node (ref "C16") (pin "2") (pinfunction "2_2") (pintype "passive"))
      (node (ref "C18") (pin "2") (pinfunction "2_2") (pintype "passive"))
      (node (ref "C19") (pin "2") (pinfunction "2_2") (pintype "passive"))
      (node (ref "C20") (pin "-") (pinfunction "-_-") (pintype "passive"))
      (node (ref "C3") (pin "2") (pinfunction "2_2") (pintype "passive"))
      (node (ref "IC1") (pin "11") (pinfunction "V-_11") (pintype "power_in"))
      (node (ref "IC2") (pin "6") (pinfunction "V-_6") (pintype "power_in"))
      (node (ref "IC3") (pin "6") (pinfunction "V-_6") (pintype "power_in"))
      (node (ref "IC4") (pin "6") (pinfunction "V-_6") (pintype "power_in"))
      (node (ref "IC5") (pin "4") (pinfunction "V-_4") (pintype "power_in"))
      (node (ref "JP2") (pin "2") (pinfunction "2_2") (pintype "passive"))
      (node (ref "R10") (pin "1") (pinfunction "1_1") (pintype "passive"))
      (node (ref "R24") (pin "1") (pinfunction "1_1") (pintype "passive"))
      (node (ref "R28") (pin "1") (pinfunction "1_1") (pintype "passive"))
      (node (ref "R40") (pin "2") (pinfunction "2_2") (pintype "passive"))
      (node (ref "R6") (pin "1") (pinfunction "1_1") (pintype "passive"))
    )
    (net (code "67") (name "unconnected-(IC2C-I_DIODE-Pad2)") (class "Default")
      (node (ref "IC2") (pin "2") (pinfunction "I_DIODE_2") (pintype "input"))
    )
    (net (code "68") (name "unconnected-(IC2D-I_DIODE-Pad15)") (class "Default")
      (node (ref "IC2") (pin "15") (pinfunction "I_DIODE_15") (pintype "input"))
    )
    (net (code "69") (name "unconnected-(IC3C-I_DIODE-Pad2)") (class "Default")
      (node (ref "IC3") (pin "2") (pinfunction "I_DIODE_2") (pintype "input"))
    )
    (net (code "70") (name "unconnected-(IC3D-I_DIODE-Pad15)") (class "Default")
      (node (ref "IC3") (pin "15") (pinfunction "I_DIODE_15") (pintype "input"))
    )
    (net (code "71") (name "unconnected-(IC4A-B-Pad7)") (class "Default")
      (node (ref "IC4") (pin "7") (pinfunction "B_7") (pintype "passive"))
    )
    (net (code "72") (name "unconnected-(IC4A-E-Pad8)") (class "Default")
      (node (ref "IC4") (pin "8") (pinfunction "E_8") (pintype "passive"))
    )
    (net (code "73") (name "unconnected-(IC4B-B-Pad10)") (class "Default")
      (node (ref "IC4") (pin "10") (pinfunction "B_10") (pintype "passive"))
    )
    (net (code "74") (name "unconnected-(IC4B-E-Pad9)") (class "Default")
      (node (ref "IC4") (pin "9") (pinfunction "E_9") (pintype "passive"))
    )
    (net (code "75") (name "unconnected-(IC4C-I_DIODE-Pad2)") (class "Default")
      (node (ref "IC4") (pin "2") (pinfunction "I_DIODE_2") (pintype "input"))
    )
    (net (code "76") (name "unconnected-(IC4D-I_DIODE-Pad15)") (class "Default")
      (node (ref "IC4") (pin "15") (pinfunction "I_DIODE_15") (pintype "input"))
    )
    (net (code "77") (name "unconnected-(IC7-AREF-Pad21)") (class "Default")
      (node (ref "IC7") (pin "21") (pinfunction "AREF_21") (pintype "passive"))
    )
    (net (code "78") (name "unconnected-(IC7-PB0(ICP)-Pad14)") (class "Default")
      (node (ref "IC7") (pin "14") (pinfunction "PB0(ICP)_14") (pintype "bidirectional"))
    )
    (net (code "79") (name "unconnected-(IC7-PB1(OC1A)-Pad15)") (class "Default")
      (node (ref "IC7") (pin "15") (pinfunction "PB1(OC1A)_15") (pintype "bidirectional"))
    )
    (net (code "80") (name "unconnected-(IC7-PC0(ADC0)-Pad23)") (class "Default")
      (node (ref "IC7") (pin "23") (pinfunction "PC0(ADC0)_23") (pintype "bidirectional"))
    )
    (net (code "81") (name "unconnected-(IC7-PC1(ADC1)-Pad24)") (class "Default")
      (node (ref "IC7") (pin "24") (pinfunction "PC1(ADC1)_24") (pintype "bidirectional"))
    )
    (net (code "82") (name "unconnected-(IC7-PC2(ADC2)-Pad25)") (class "Default")
      (node (ref "IC7") (pin "25") (pinfunction "PC2(ADC2)_25") (pintype "bidirectional"))
    )
    (net (code "83") (name "unconnected-(IC7-PC3(ADC3)-Pad26)") (class "Default")
      (node (ref "IC7") (pin "26") (pinfunction "PC3(ADC3)_26") (pintype "bidirectional"))
    )
    (net (code "84") (name "unconnected-(IC7-PD0(RXD)-Pad2)") (class "Default")
      (node (ref "IC7") (pin "2") (pinfunction "PD0(RXD)_2") (pintype "bidirectional"))
    )
    (net (code "85") (name "unconnected-(IC7-PD3(INT1)-Pad5)") (class "Default")
      (node (ref "IC7") (pin "5") (pinfunction "PD3(INT1)_5") (pintype "bidirectional"))
    )
    (net (code "86") (name "unconnected-(IC7-PD7(AIN1)-Pad13)") (class "Default")
      (node (ref "IC7") (pin "13") (pinfunction "PD7(AIN1)_13") (pintype "bidirectional"))
    )
  )
)
